# Power.net
KiCad netlist of a schematic drawn in Altium Designer
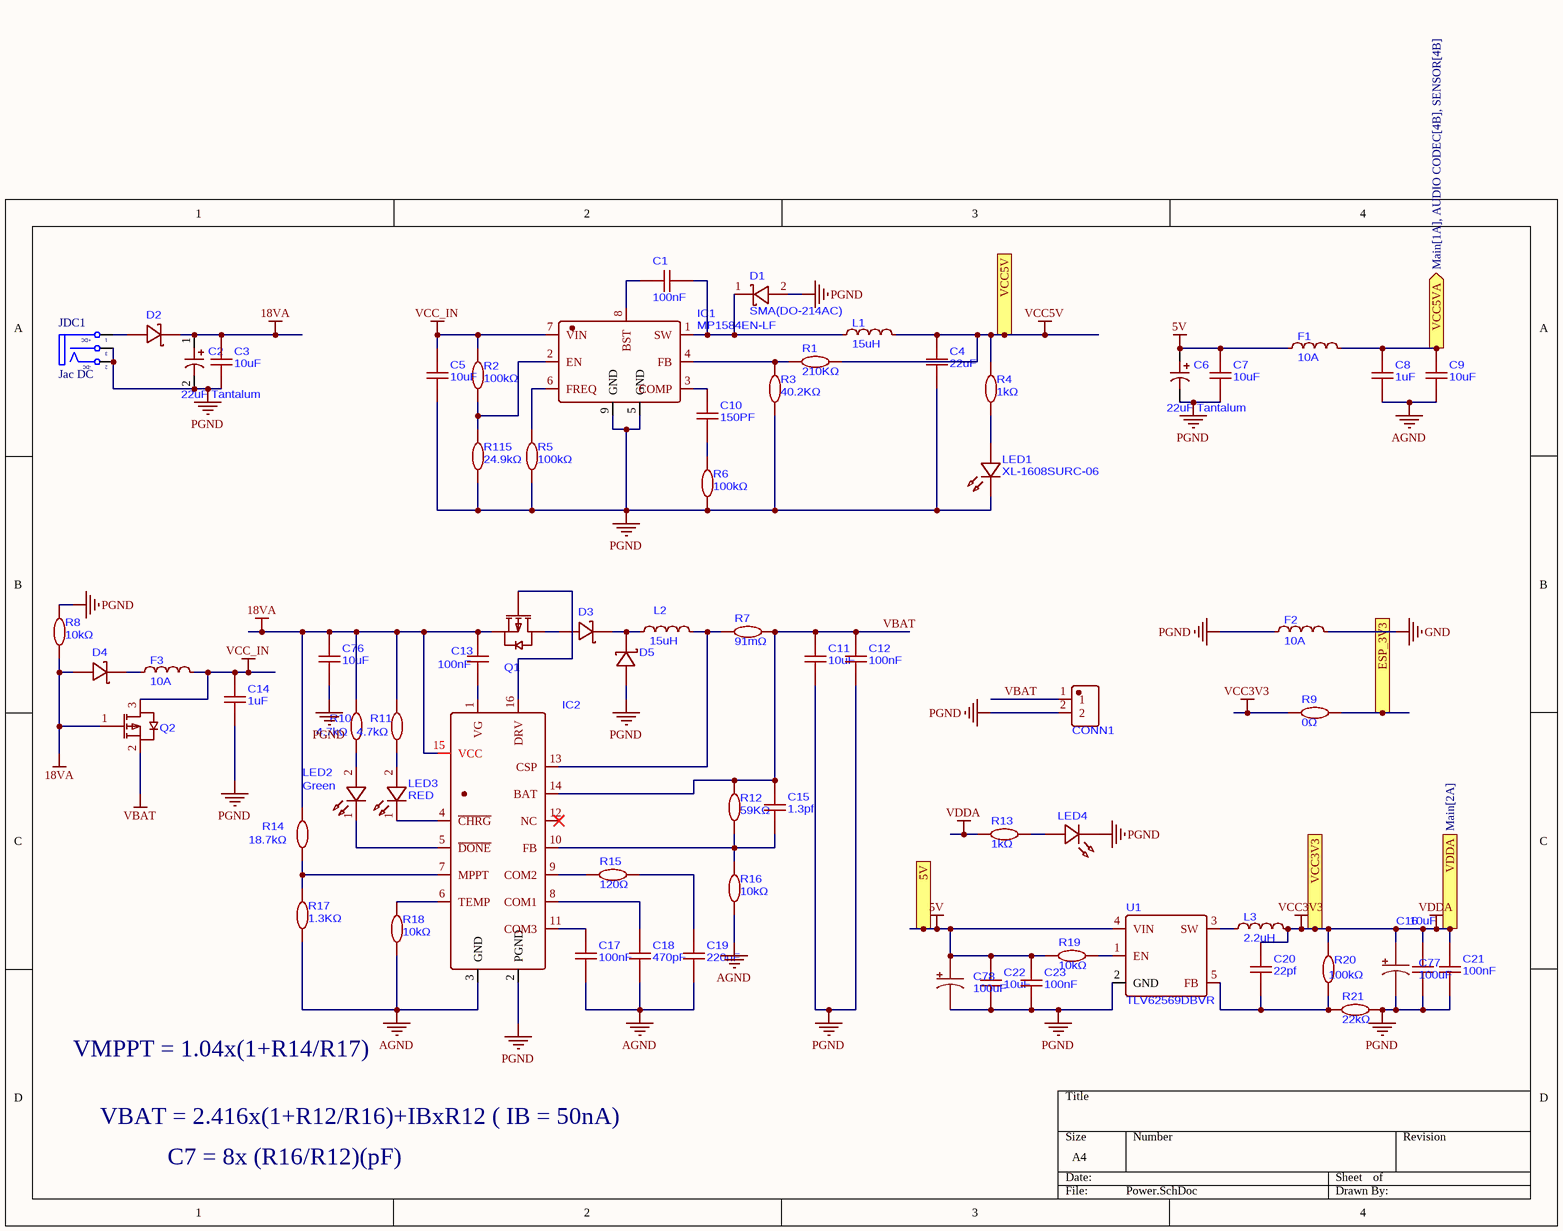
[diagram p0: Power.SchDoc]

(export (version "E")
  (design (tool "Eeschema 10.0.6"))
  (components
    (comp (ref "C1")
      (value "100nF")
      (footprint "C0603")
      (description "50V 100nF X7R ±10% 0603 Ceramic Capacitors ROHS")
      (libsource (lib "Schlib2") (part "CC0603KRX7R9BB104"))
    )
    (comp (ref "C2")
      (value "22uF Tantalum")
      (footprint "CAP-SMD_L7.3-W4.3-R-RD")
      (description "CAP TANT 22uF ±10% 50V CASE-X-7343-43(mm)")
      (libsource (lib "") (part "T491X226K050AT_1"))
    )
    (comp (ref "C3")
      (value "10uF")
      (footprint "C0603")
      (description "25V 10uF X5R ±20% 0603 Ceramic Capacitors ROHS")
      (libsource (lib "Schlib2") (part "CL10A106MA8NRNC"))
    )
    (comp (ref "C4")
      (value "22uF")
      (footprint "C0603")
      (description "10V 22uF X5R ±20% 0603 Ceramic Capacitors ROHS")
      (libsource (lib "Schlib2") (part "CL10A226MP8NUNE"))
    )
    (comp (ref "C5")
      (value "10uF")
      (footprint "C0603")
      (description "25V 10uF X5R ±20% 0603 Ceramic Capacitors ROHS")
      (libsource (lib "Schlib2") (part "CL10A106MA8NRNC"))
    )
    (comp (ref "C6")
      (value "22uF Tantalum")
      (footprint "CAP-SMD_L7.3-W4.3-R-RD")
      (description "CAP TANT 22uF ±10% 50V CASE-X-7343-43(mm)")
      (libsource (lib "Schlib2") (part "T491X226K050AT"))
    )
    (comp (ref "C7")
      (value "10uF")
      (footprint "C0603")
      (description "25V 10uF X5R ±20% 0603 Ceramic Capacitors ROHS")
      (libsource (lib "Schlib2") (part "CL10A106MA8NRNC"))
    )
    (comp (ref "C8")
      (value "1uF")
      (footprint "C0603")
      (description "25V 1uF X7R ±10% 0603 Ceramic Capacitors ROHS")
      (libsource (lib "Schlib2") (part "CL10B105KA8NNNC"))
    )
    (comp (ref "C9")
      (value "10uF")
      (footprint "C0603")
      (description "25V 10uF X5R ±20% 0603 Ceramic Capacitors ROHS")
      (libsource (lib "Schlib2") (part "CL10A106MA8NRNC"))
    )
    (comp (ref "C10")
      (value "150PF")
      (footprint "C0603")
      (description "50V 150pF NP0 ±5% 0603 Ceramic Capacitors ROHS")
      (libsource (lib "Schlib2") (part "CC0603JRNPO9BN151"))
    )
    (comp (ref "C11")
      (value "10uF")
      (footprint "C0603")
      (description "25V 10uF X5R ±20% 0603 Ceramic Capacitors ROHS")
      (libsource (lib "Schlib2") (part "CL10A106MA8NRNC"))
    )
    (comp (ref "C12")
      (value "100nF")
      (footprint "C0603")
      (description "50V 100nF X7R ±10% 0603 Ceramic Capacitors ROHS")
      (libsource (lib "Schlib2") (part "CC0603KRX7R9BB104"))
    )
    (comp (ref "C13")
      (value "100nF")
      (footprint "C0603")
      (description "50V 100nF X7R ±10% 0603 Ceramic Capacitors ROHS")
      (libsource (lib "Schlib2") (part "CC0603KRX7R9BB104"))
    )
    (comp (ref "C14")
      (value "1uF")
      (footprint "C0603")
      (description "25V 1uF X7R ±10% 0603 Ceramic Capacitors ROHS")
      (libsource (lib "Schlib2") (part "CL10B105KA8NNNC"))
    )
    (comp (ref "C15")
      (value "1.3pf")
      (footprint "C0603")
      (description "50V 1.3pF NP0 0603 Ceramic Capacitors ROHS")
      (libsource (lib "Schlib2") (part "CC0603CRNPO9BN1R3"))
    )
    (comp (ref "C16")
      (value "10uF")
      (footprint "C0603")
      (description "10V 10uF X5R ±10% 0603 Ceramic Capacitors ROHS")
      (libsource (lib "Schlib2") (part "CL10A106KP8NNNC"))
    )
    (comp (ref "C17")
      (value "100nF")
      (footprint "C0603")
      (description "50V 100nF X7R ±10% 0603 Ceramic Capacitors ROHS")
      (libsource (lib "Schlib2") (part "CC0603KRX7R9BB104"))
    )
    (comp (ref "C18")
      (value "470pF")
      (footprint "C0603")
      (description "50V 470pF C0G ±5% 0603 Ceramic Capacitors ROHS")
      (libsource (lib "Schlib2") (part "CL10C471JB8NNNC"))
    )
    (comp (ref "C19")
      (value "220nF")
      (footprint "C0603")
      (description "50V 220nF X7R ±10% 0603 Ceramic Capacitors ROHS")
      (libsource (lib "Schlib2") (part "CL10B224KB8NNNC"))
    )
    (comp (ref "C20")
      (value "22pf")
      (footprint "C0603")
      (description "50V 22pF C0G ±5% 0603 Ceramic Capacitors RoHS")
      (libsource (lib "Schlib2") (part "CL10C220JB8NNNC"))
    )
    (comp (ref "C21")
      (value "100nF")
      (footprint "C0603")
      (description "50V 100nF X7R ±10% 0603 Ceramic Capacitors ROHS")
      (libsource (lib "Schlib2") (part "CC0603KRX7R9BB104"))
    )
    (comp (ref "C22")
      (value "10uF")
      (footprint "C0603")
      (description "10V 10uF X5R ±10% 0603 Ceramic Capacitors ROHS")
      (libsource (lib "Schlib2") (part "CL10A106KP8NNNC"))
    )
    (comp (ref "C23")
      (value "100nF")
      (footprint "C0603")
      (description "50V 100nF X7R ±10% 0603 Ceramic Capacitors ROHS")
      (libsource (lib "Schlib2") (part "CC0603KRX7R9BB104"))
    )
    (comp (ref "C76")
      (value "10uF")
      (footprint "C0603")
      (description "25V 10uF X5R ±20% 0603 Ceramic Capacitors ROHS")
      (libsource (lib "Schlib2") (part "CL10A106MA8NRNC"))
    )
    (comp (ref "C77")
      (value "100uF")
      (footprint "CAP-SMD_L3.5-W2.8-R-RD")
      (description "100uF 10V ±10% CASE-B-3528-19(mm) Tantalum Capacitors RoHS")
      (libsource (lib "Schlib2") (part "CA45A-B-10V-100UF-K"))
    )
    (comp (ref "C78")
      (value "100uF")
      (footprint "CAP-SMD_L3.5-W2.8-R-RD")
      (description "100uF 10V ±10% CASE-B-3528-19(mm) Tantalum Capacitors RoHS")
      (libsource (lib "Schlib2") (part "CA45A-B-10V-100UF-K"))
    )
    (comp (ref "CONN1")
      (value "TERM BLK 2POS 5mm TH")
      (footprint "CONN-TH_P5.00_KF128-5.0-2P")
      (libsource (lib "Schlib2") (part "KF128-5.0-2P"))
    )
    (comp (ref "D1")
      (value "SMA(DO-214AC)")
      (footprint "SMA_L4.4-W2.6-LS5.0-RD")
      (description "80A 40V 500mV@3A 3A SMA(DO-214AC) Single Diodes ROHS")
      (libsource (lib "Schlib2") (part "B340A-13-F"))
    )
    (comp (ref "D2")
      (value "B540CQ-13-F")
      (footprint "SMC_L6.9-W5.9-LS7.9-RD")
      (description "40V 550mV@5A 5A SMC(DO-214AB) Single Diodes ROHS")
      (libsource (lib "Schlib2") (part "B540CQ-13-F"))
    )
    (comp (ref "D3")
      (value "B540CQ-13-F")
      (footprint "SMC_L6.9-W5.9-LS7.9-RD")
      (description "40V 550mV@5A 5A SMC(DO-214AB) Single Diodes ROHS")
      (libsource (lib "Schlib2") (part "B540CQ-13-F"))
    )
    (comp (ref "D4")
      (value "B540CQ-13-F")
      (footprint "SMC_L6.9-W5.9-LS7.9-RD")
      (description "40V 550mV@5A 5A SMC(DO-214AB) Single Diodes ROHS")
      (libsource (lib "Schlib2") (part "B540CQ-13-F"))
    )
    (comp (ref "D5")
      (value "B540CQ-13-F")
      (footprint "SMC_L6.9-W5.9-LS7.9-RD")
      (description "40V 550mV@5A 5A SMC(DO-214AB) Single Diodes ROHS")
      (libsource (lib "Schlib2") (part "B540CQ-13-F"))
    )
    (comp (ref "F1")
      (value "10A")
      (footprint "IND-SMD_L8.5-W3.1")
      (description "4mΩ 100Ω@100MHz SMD,8.5x3.1mm Ferrite Beads and Chips ROHS")
      (libsource (lib "Schlib2") (part "HI3312X101R-10"))
    )
    (comp (ref "F2")
      (value "10A")
      (footprint "IND-SMD_L8.5-W3.1")
      (description "4mΩ 100Ω@100MHz SMD,8.5x3.1mm Ferrite Beads and Chips ROHS")
      (libsource (lib "Schlib2") (part "HI3312X101R-10"))
    )
    (comp (ref "F3")
      (value "10A")
      (footprint "IND-SMD_L8.5-W3.1")
      (description "4mΩ 100Ω@100MHz SMD,8.5x3.1mm Ferrite Beads and Chips ROHS")
      (libsource (lib "Schlib2") (part "HI3312X101R-10"))
    )
    (comp (ref "IC1")
      (value "MP1584EN-LF")
      (footprint "SOIC-8_L4.9-W3.9-P1.27-LS6.0-BL-EP3.3")
      (description "Buck Switching Regulator IC")
      (libsource (lib "Schlib2") (part "MP1584EN-LF"))
    )
    (comp (ref "IC2")
      (value "5A TSSOP-16 Battery Management ROHS")
      (footprint "TSSOP-16_L5.0-W4.4-P0.65-LS6.4-BL")
      (libsource (lib "Schlib2") (part "CN3722"))
    )
    (comp (ref "JDC1")
      (value "Jac DC")
      (footprint "DC-IN")
      (description "Jac DC input")
      (libsource (lib "syhaunguyen") (part "DCIN"))
    )
    (comp (ref "L1")
      (value "15uH")
      (footprint "IND-SMD_L10.1-W10.0")
      (description "3.4A 15uH Magnetic Shielded Inductor ±20% 41mΩ SMD,10.1x10.1mm Fixed Inductors ROHS")
      (libsource (lib "Schlib2") (part "YDRH105R-150M"))
    )
    (comp (ref "L2")
      (value "15uH")
      (footprint "IND-SMD_L10.1-W10.0")
      (description "3.4A 15uH Magnetic Shielded Inductor ±20% 41mΩ SMD,10.1x10.1mm Fixed Inductors ROHS")
      (libsource (lib "Schlib2") (part "YDRH105R-150M"))
    )
    (comp (ref "L3")
      (value "2.2uH")
      (footprint "IND-SMD_L5.4-W5.2")
      (description "7A 2.2uH Molded Inductor ±20% 7A 29mΩ SMD,5.4x5.2mm Fixed Inductors RoHS")
      (libsource (lib "Schlib2") (part "APH0530T2R2M"))
    )
    (comp (ref "LED1")
      (value "XL-1608SURC-06")
      (footprint "LED0603-RD_RED")
      (description "20mA 2.3V Red 50mW 0603 LED Indication - Discrete ROHS")
      (libsource (lib "Schlib2") (part "XL-1608SURC-06"))
    )
    (comp (ref "LED2")
      (value "Green")
      (footprint "LED0603-RD_RED")
      (description "5mA 500mcd 526nm~532nm Green 70mW 2.8V 0603 LED Indication - Discrete ROHS")
      (libsource (lib "Schlib2") (part "D-060306G1/SS2/G1"))
    )
    (comp (ref "LED3")
      (value "RED")
      (footprint "LED0603-RD_RED")
      (description "20mA 2.3V Red 50mW 0603 LED Indication - Discrete ROHS")
      (libsource (lib "") (part "XL-1608SURC-06_1"))
    )
    (comp (ref "LED4")
      (value "XL-1608SURC-06")
      (footprint "LED0603-RD_RED")
      (description "20mA 2.3V Red 50mW 0603 LED Indication - Discrete ROHS")
      (libsource (lib "Schlib2") (part "XL-1608SURC-06"))
    )
    (comp (ref "Q1")
      (value "MOSFET P-CH 30V 4.3A SOT-23")
      (footprint "SOT-23-3_L2.9-W1.6-P1.90-LS2.8-BR")
      (description "30V 4.3A 48mΩ@10V 2.5V@250uA 1 P-Channel SOT-23 Single FETs, MOSFETs ROHS")
      (libsource (lib "") (part "AO3407A_1"))
    )
    (comp (ref "Q2")
      (value "MOSFET P-CH 30V 4.3A SOT-23")
      (footprint "SOT-23-3_L2.9-W1.6-P1.90-LS2.8-BR")
      (description "30V 4.3A 48mΩ@10V 2.5V@250uA 1 P-Channel SOT-23 Single FETs, MOSFETs ROHS")
      (libsource (lib "Schlib2") (part "AO3407A"))
    )
    (comp (ref "R1")
      (value "210KΩ")
      (footprint "R0603")
      (description "100mW 210kΩ 75V ±100ppm/℃ Thick Film Resistor ±1% 0603 Chip Resistor - Surface Mount ROHS")
      (libsource (lib "Schlib2") (part "0603WAF2103T5E"))
    )
    (comp (ref "R2")
      (value "100kΩ")
      (footprint "R0603")
      (description "100mW 100kΩ 75V ±100ppm/℃ Thick Film Resistor ±1% 0603 Chip Resistor - Surface Mount ROHS")
      (libsource (lib "Schlib2") (part "RC0603FR-07100KL"))
    )
    (comp (ref "R3")
      (value "40.2KΩ")
      (footprint "R0603")
      (description "40.2kΩ 100mW 75V ±25ppm/℃ Thin Film Resistor ±0.1% 0603 Chip Resistor - Surface Mount ROHS")
      (libsource (lib "Schlib2") (part "RT0603BRD0740K2L"))
    )
    (comp (ref "R4")
      (value "1kΩ")
      (footprint "R0603")
      (description "100mW 1kΩ 50V ±100ppm/℃ Thick Film Resistor ±5% 0603 Chip Resistor - Surface Mount ROHS")
      (libsource (lib "Schlib2") (part "RMC 0603 1K J N"))
    )
    (comp (ref "R5")
      (value "100kΩ")
      (footprint "R0603")
      (description "100mW 100kΩ 75V ±100ppm/℃ Thick Film Resistor ±1% 0603 Chip Resistor - Surface Mount ROHS")
      (libsource (lib "Schlib2") (part "RC0603FR-07100KL"))
    )
    (comp (ref "R6")
      (value "100kΩ")
      (footprint "R0603")
      (description "100mW 100kΩ 75V ±100ppm/℃ Thick Film Resistor ±1% 0603 Chip Resistor - Surface Mount ROHS")
      (libsource (lib "Schlib2") (part "RC0603FR-07100KL"))
    )
    (comp (ref "R7")
      (value "91mΩ")
      (footprint "R1206")
      (description "250mW 91mΩ 500V ±600ppm/℃ Thick Film Resistor ±1% 1206 Chip Resistor - Surface Mount ROHS")
      (libsource (lib "Schlib2") (part "FRL1206FR091TS"))
    )
    (comp (ref "R8")
      (value "10kΩ")
      (footprint "R0603")
      (description "100mW 10kΩ 75V ±100ppm/℃ Thick Film Resistor ±1% 0603 Chip Resistor - Surface Mount ROHS")
      (libsource (lib "Schlib2") (part "RC0603FR-0710KL"))
    )
    (comp (ref "R9")
      (value "0Ω")
      (footprint "R0603")
      (description "100mW 0Ω 75V Thick Film Resistor ±5% 0603 Chip Resistor - Surface Mount RoHS")
      (libsource (lib "Schlib2") (part "RC0603JR-070RL"))
    )
    (comp (ref "R10")
      (value "4.7kΩ")
      (footprint "R0603")
      (description "100mW 4.7kΩ 75V ±100ppm/℃ Thick Film Resistor ±1% 0603 Chip Resistor - Surface Mount ROHS")
      (libsource (lib "Schlib2") (part "RC0603FR-074K7L"))
    )
    (comp (ref "R11")
      (value "4.7kΩ")
      (footprint "R0603")
      (description "100mW 4.7kΩ 75V ±100ppm/℃ Thick Film Resistor ±1% 0603 Chip Resistor - Surface Mount ROHS")
      (libsource (lib "Schlib2") (part "RC0603FR-074K7L"))
    )
    (comp (ref "R12")
      (value "59KΩ")
      (footprint "R0603")
      (description "100mW 59kΩ 75V ±100ppm/℃ Thick Film Resistor ±1% 0603 Chip Resistor - Surface Mount ROHS")
      (libsource (lib "Schlib2") (part "FRC0603F5902TS"))
    )
    (comp (ref "R13")
      (value "1kΩ")
      (footprint "R0603")
      (description "100mW 1kΩ 50V ±100ppm/℃ Thick Film Resistor ±5% 0603 Chip Resistor - Surface Mount ROHS")
      (libsource (lib "Schlib2") (part "RMC 0603 1K J N"))
    )
    (comp (ref "R14")
      (value "18.7kΩ")
      (footprint "R0603")
      (description "100mW 18.7kΩ 75V ±100ppm/℃ Thick Film Resistor ±1% 0603 Chip Resistor - Surface Mount ROHS")
      (libsource (lib "Schlib2") (part "FRC0603F1872TS"))
    )
    (comp (ref "R15")
      (value "120Ω")
      (footprint "R0603")
      (description "100mW 120Ω 75V ±100ppm/℃ Thick Film Resistor ±1% 0603 Chip Resistor - Surface Mount ROHS")
      (libsource (lib "Schlib2") (part "0603WAF1200T5E"))
    )
    (comp (ref "R16")
      (value "10kΩ")
      (footprint "R0603")
      (description "100mW 10kΩ 75V ±100ppm/℃ Thick Film Resistor ±1% 0603 Chip Resistor - Surface Mount ROHS")
      (libsource (lib "Schlib2") (part "RC0603FR-0710KL"))
    )
    (comp (ref "R17")
      (value "1.3KΩ")
      (footprint "R0603")
      (description "100mW 1.3kΩ 75V ±25ppm/℃ Thin Film Resistor ±0.1% 0603 Chip Resistor - Surface Mount ROHS")
      (libsource (lib "Schlib2") (part "RT0603BRD071K3L"))
    )
    (comp (ref "R18")
      (value "10kΩ")
      (footprint "R0603")
      (description "100mW 10kΩ 75V ±100ppm/℃ Thick Film Resistor ±1% 0603 Chip Resistor - Surface Mount ROHS")
      (libsource (lib "Schlib2") (part "RC0603FR-0710KL"))
    )
    (comp (ref "R19")
      (value "10kΩ")
      (footprint "R0603")
      (description "100mW 10kΩ 75V ±100ppm/℃ Thick Film Resistor ±1% 0603 Chip Resistor - Surface Mount ROHS")
      (libsource (lib "Schlib2") (part "RC0603FR-0710KL"))
    )
    (comp (ref "R20")
      (value "100kΩ")
      (footprint "R0603")
      (description "100mW 100kΩ 75V ±100ppm/℃ Thick Film Resistor ±1% 0603 Chip Resistor - Surface Mount ROHS")
      (libsource (lib "Schlib2") (part "RC0603FR-07100KL"))
    )
    (comp (ref "R21")
      (value "22kΩ")
      (footprint "R0603")
      (description "100mW 22kΩ 75V ±100ppm/℃ Thick Film Resistor ±1% 0603 Chip Resistor - Surface Mount RoHS")
      (libsource (lib "Schlib2") (part "RC0603FR-0722KL"))
    )
    (comp (ref "R115")
      (value "24.9kΩ")
      (footprint "R0603")
      (description "1100mW 24.9kΩ 75V ±100ppm/℃ Thick Film Resistor ±1% 0603 Chip Resistor - Surface Mount ROHS")
      (libsource (lib "Schlib2") (part "0603WAF2492T5E"))
    )
    (comp (ref "U1")
      (value "TLV62569DBVR")
      (footprint "SOT-23-5_L3.0-W1.7-P0.95-LS2.8-BR")
      (libsource (lib "Schlib2") (part "TLV62569DBVR"))
    )
  )
  (nets
    (net (code "1") (name "/ESP_3V3") (class "Default")
      (node (ref "R9") (pin "2") (pinfunction "2_2") (pintype "passive"))
    )
    (net (code "2") (name "/VCC5VA") (class "Default")
      (node (ref "C8") (pin "1") (pinfunction "1_1") (pintype "passive"))
      (node (ref "C9") (pin "2") (pinfunction "2_2") (pintype "passive"))
      (node (ref "F1") (pin "2") (pinfunction "2_2") (pintype "passive"))
    )
    (net (code "3") (name "5V") (class "Default")
      (node (ref "C22") (pin "2") (pinfunction "2_2") (pintype "passive"))
      (node (ref "C23") (pin "2") (pinfunction "2_2") (pintype "passive"))
      (node (ref "C6") (pin "1") (pinfunction "1_1") (pintype "passive"))
      (node (ref "C7") (pin "2") (pinfunction "2_2") (pintype "passive"))
      (node (ref "C78") (pin "1") (pinfunction "1_1") (pintype "passive"))
      (node (ref "F1") (pin "1") (pinfunction "1_1") (pintype "passive"))
      (node (ref "R19") (pin "1") (pinfunction "1_1") (pintype "passive"))
      (node (ref "U1") (pin "4") (pinfunction "VIN_4") (pintype "passive"))
    )
    (net (code "4") (name "18VA") (class "Default")
      (node (ref "C13") (pin "2") (pinfunction "2_2") (pintype "passive"))
      (node (ref "C2") (pin "1") (pinfunction "1_1") (pintype "passive"))
      (node (ref "C3") (pin "2") (pinfunction "2_2") (pintype "passive"))
      (node (ref "C76") (pin "2") (pinfunction "2_2") (pintype "passive"))
      (node (ref "D2") (pin "1") (pinfunction "C_1") (pintype "passive"))
      (node (ref "D4") (pin "2") (pinfunction "A_2") (pintype "passive"))
      (node (ref "IC2") (pin "15") (pinfunction "VCC_15") (pintype "passive"))
      (node (ref "Q1") (pin "2") (pinfunction "S_2") (pintype "passive"))
      (node (ref "Q2") (pin "1") (pinfunction "G_1") (pintype "passive"))
      (node (ref "R10") (pin "2") (pinfunction "2_2") (pintype "passive"))
      (node (ref "R11") (pin "2") (pinfunction "2_2") (pintype "passive"))
      (node (ref "R14") (pin "2") (pinfunction "2_2") (pintype "passive"))
      (node (ref "R8") (pin "1") (pinfunction "1_1") (pintype "passive"))
    )
    (net (code "5") (name "AGND") (class "Default")
      (node (ref "C17") (pin "1") (pinfunction "1_1") (pintype "passive"))
      (node (ref "C18") (pin "1") (pinfunction "1_1") (pintype "passive"))
      (node (ref "C19") (pin "1") (pinfunction "1_1") (pintype "passive"))
      (node (ref "C8") (pin "2") (pinfunction "2_2") (pintype "passive"))
      (node (ref "C9") (pin "1") (pinfunction "1_1") (pintype "passive"))
      (node (ref "IC2") (pin "3") (pinfunction "GND_3") (pintype "passive"))
      (node (ref "R16") (pin "1") (pinfunction "1_1") (pintype "passive"))
      (node (ref "R17") (pin "1") (pinfunction "1_1") (pintype "passive"))
      (node (ref "R18") (pin "1") (pinfunction "1_1") (pintype "passive"))
    )
    (net (code "6") (name "GND") (class "Default")
      (node (ref "F2") (pin "2") (pinfunction "2_2") (pintype "passive"))
    )
    (net (code "7") (name "Net-(C10-Pad1)") (class "Default")
      (node (ref "C10") (pin "1") (pinfunction "1_1") (pintype "passive"))
      (node (ref "R6") (pin "2") (pinfunction "2_2") (pintype "passive"))
    )
    (net (code "8") (name "Net-(C19-Pad2)") (class "Default")
      (node (ref "C19") (pin "2") (pinfunction "2_2") (pintype "passive"))
      (node (ref "R15") (pin "2") (pinfunction "2_2") (pintype "passive"))
    )
    (net (code "9") (name "Net-(D1-K)") (class "Default")
      (node (ref "C1") (pin "2") (pinfunction "2_2") (pintype "passive"))
      (node (ref "D1") (pin "1") (pinfunction "K_1") (pintype "passive"))
      (node (ref "IC1") (pin "1") (pinfunction "SW_1") (pintype "passive"))
      (node (ref "L1") (pin "1") (pinfunction "1_1") (pintype "passive"))
    )
    (net (code "10") (name "Net-(D2-A)") (class "Default")
      (node (ref "D2") (pin "2") (pinfunction "A_2") (pintype "passive"))
      (node (ref "JDC1") (pin "1") (pinfunction "T_1") (pintype "passive"))
    )
    (net (code "11") (name "Net-(D3-A)") (class "Default")
      (node (ref "D3") (pin "2") (pinfunction "A_2") (pintype "passive"))
      (node (ref "Q1") (pin "3") (pinfunction "D_3") (pintype "passive"))
    )
    (net (code "12") (name "Net-(D3-C)") (class "Default")
      (node (ref "D3") (pin "1") (pinfunction "C_1") (pintype "passive"))
      (node (ref "D5") (pin "1") (pinfunction "C_1") (pintype "passive"))
      (node (ref "L2") (pin "1") (pinfunction "1_1") (pintype "passive"))
    )
    (net (code "13") (name "Net-(D4-C)") (class "Default")
      (node (ref "D4") (pin "1") (pinfunction "C_1") (pintype "passive"))
      (node (ref "F3") (pin "1") (pinfunction "1_1") (pintype "passive"))
    )
    (net (code "14") (name "Net-(IC1-BST)") (class "Default")
      (node (ref "C1") (pin "1") (pinfunction "1_1") (pintype "passive"))
      (node (ref "IC1") (pin "8") (pinfunction "BST_8") (pintype "passive"))
    )
    (net (code "15") (name "Net-(IC1-COMP)") (class "Default")
      (node (ref "C10") (pin "2") (pinfunction "2_2") (pintype "passive"))
      (node (ref "IC1") (pin "3") (pinfunction "COMP_3") (pintype "passive"))
    )
    (net (code "16") (name "Net-(IC1-EN)") (class "Default")
      (node (ref "IC1") (pin "2") (pinfunction "EN_2") (pintype "passive"))
      (node (ref "R115") (pin "2") (pinfunction "2_2") (pintype "passive"))
      (node (ref "R2") (pin "1") (pinfunction "1_1") (pintype "passive"))
    )
    (net (code "17") (name "Net-(IC1-FB)") (class "Default")
      (node (ref "IC1") (pin "4") (pinfunction "FB_4") (pintype "passive"))
      (node (ref "R1") (pin "1") (pinfunction "1_1") (pintype "passive"))
      (node (ref "R3") (pin "2") (pinfunction "2_2") (pintype "passive"))
    )
    (net (code "18") (name "Net-(IC1-FREQ)") (class "Default")
      (node (ref "IC1") (pin "6") (pinfunction "FREQ_6") (pintype "passive"))
      (node (ref "R5") (pin "2") (pinfunction "2_2") (pintype "passive"))
    )
    (net (code "19") (name "Net-(IC2-COM1)") (class "Default")
      (node (ref "C18") (pin "2") (pinfunction "2_2") (pintype "passive"))
      (node (ref "IC2") (pin "8") (pinfunction "COM1_8") (pintype "passive"))
    )
    (net (code "20") (name "Net-(IC2-COM2)") (class "Default")
      (node (ref "IC2") (pin "9") (pinfunction "COM2_9") (pintype "passive"))
      (node (ref "R15") (pin "1") (pinfunction "1_1") (pintype "passive"))
    )
    (net (code "21") (name "Net-(IC2-COM3)") (class "Default")
      (node (ref "C17") (pin "2") (pinfunction "2_2") (pintype "passive"))
      (node (ref "IC2") (pin "11") (pinfunction "COM3_11") (pintype "passive"))
    )
    (net (code "22") (name "Net-(IC2-CSP)") (class "Default")
      (node (ref "IC2") (pin "13") (pinfunction "CSP_13") (pintype "passive"))
      (node (ref "L2") (pin "2") (pinfunction "2_2") (pintype "passive"))
      (node (ref "R7") (pin "1") (pinfunction "1_1") (pintype "passive"))
    )
    (net (code "23") (name "Net-(IC2-DRV)") (class "Default")
      (node (ref "IC2") (pin "16") (pinfunction "DRV_16") (pintype "passive"))
      (node (ref "Q1") (pin "1") (pinfunction "G_1") (pintype "passive"))
    )
    (net (code "24") (name "Net-(IC2-FB)") (class "Default")
      (node (ref "C15") (pin "1") (pinfunction "1_1") (pintype "passive"))
      (node (ref "IC2") (pin "10") (pinfunction "FB_10") (pintype "passive"))
      (node (ref "R12") (pin "1") (pinfunction "1_1") (pintype "passive"))
      (node (ref "R16") (pin "2") (pinfunction "2_2") (pintype "passive"))
    )
    (net (code "25") (name "Net-(IC2-MPPT)") (class "Default")
      (node (ref "IC2") (pin "7") (pinfunction "MPPT_7") (pintype "passive"))
      (node (ref "R14") (pin "1") (pinfunction "1_1") (pintype "passive"))
      (node (ref "R17") (pin "2") (pinfunction "2_2") (pintype "passive"))
    )
    (net (code "26") (name "Net-(IC2-TEMP)") (class "Default")
      (node (ref "IC2") (pin "6") (pinfunction "TEMP_6") (pintype "passive"))
      (node (ref "R18") (pin "2") (pinfunction "2_2") (pintype "passive"))
    )
    (net (code "27") (name "Net-(IC2-VG)") (class "Default")
      (node (ref "C13") (pin "1") (pinfunction "1_1") (pintype "passive"))
      (node (ref "IC2") (pin "1") (pinfunction "VG_1") (pintype "passive"))
    )
    (net (code "28") (name "Net-(IC2-~{CHRG})") (class "Default")
      (node (ref "IC2") (pin "4") (pinfunction "~{CHRG}_4") (pintype "passive"))
      (node (ref "LED3") (pin "1") (pinfunction "K_1") (pintype "passive"))
    )
    (net (code "29") (name "Net-(IC2-~{DONE})") (class "Default")
      (node (ref "IC2") (pin "5") (pinfunction "~{DONE}_5") (pintype "passive"))
      (node (ref "LED2") (pin "1") (pinfunction "K_1") (pintype "passive"))
    )
    (net (code "30") (name "Net-(LED1-A)") (class "Default")
      (node (ref "LED1") (pin "2") (pinfunction "A_2") (pintype "passive"))
      (node (ref "R4") (pin "1") (pinfunction "1_1") (pintype "passive"))
    )
    (net (code "31") (name "Net-(LED2-A)") (class "Default")
      (node (ref "LED2") (pin "2") (pinfunction "A_2") (pintype "passive"))
      (node (ref "R10") (pin "1") (pinfunction "1_1") (pintype "passive"))
    )
    (net (code "32") (name "Net-(LED3-A)") (class "Default")
      (node (ref "LED3") (pin "2") (pinfunction "A_2") (pintype "passive"))
      (node (ref "R11") (pin "1") (pinfunction "1_1") (pintype "passive"))
    )
    (net (code "33") (name "Net-(LED4-A)") (class "Default")
      (node (ref "LED4") (pin "2") (pinfunction "A_2") (pintype "passive"))
      (node (ref "R13") (pin "1") (pinfunction "1_1") (pintype "passive"))
    )
    (net (code "34") (name "Net-(U1-EN)") (class "Default")
      (node (ref "R19") (pin "2") (pinfunction "2_2") (pintype "passive"))
      (node (ref "U1") (pin "1") (pinfunction "EN_1") (pintype "passive"))
    )
    (net (code "35") (name "Net-(U1-FB)") (class "Default")
      (node (ref "C20") (pin "1") (pinfunction "1_1") (pintype "passive"))
      (node (ref "R20") (pin "1") (pinfunction "1_1") (pintype "passive"))
      (node (ref "R21") (pin "1") (pinfunction "1_1") (pintype "passive"))
      (node (ref "U1") (pin "5") (pinfunction "FB_5") (pintype "passive"))
    )
    (net (code "36") (name "Net-(U1-SW)") (class "Default")
      (node (ref "L3") (pin "1") (pinfunction "1_1") (pintype "passive"))
      (node (ref "U1") (pin "3") (pinfunction "SW_3") (pintype "passive"))
    )
    (net (code "37") (name "PGND") (class "Default")
      (node (ref "C11") (pin "1") (pinfunction "1_1") (pintype "passive"))
      (node (ref "C12") (pin "1") (pinfunction "1_1") (pintype "passive"))
      (node (ref "C14") (pin "2") (pinfunction "2_2") (pintype "passive"))
      (node (ref "C16") (pin "1") (pinfunction "1_1") (pintype "passive"))
      (node (ref "C2") (pin "2") (pinfunction "2_2") (pintype "passive"))
      (node (ref "C21") (pin "1") (pinfunction "1_1") (pintype "passive"))
      (node (ref "C22") (pin "1") (pinfunction "1_1") (pintype "passive"))
      (node (ref "C23") (pin "1") (pinfunction "1_1") (pintype "passive"))
      (node (ref "C3") (pin "1") (pinfunction "1_1") (pintype "passive"))
      (node (ref "C4") (pin "1") (pinfunction "1_1") (pintype "passive"))
      (node (ref "C5") (pin "1") (pinfunction "1_1") (pintype "passive"))
      (node (ref "C6") (pin "2") (pinfunction "2_2") (pintype "passive"))
      (node (ref "C7") (pin "1") (pinfunction "1_1") (pintype "passive"))
      (node (ref "C76") (pin "1") (pinfunction "1_1") (pintype "passive"))
      (node (ref "C77") (pin "2") (pinfunction "2_2") (pintype "passive"))
      (node (ref "C78") (pin "2") (pinfunction "2_2") (pintype "passive"))
      (node (ref "CONN1") (pin "2") (pinfunction "2_2") (pintype "passive"))
      (node (ref "D1") (pin "2") (pinfunction "A_2") (pintype "passive"))
      (node (ref "D5") (pin "2") (pinfunction "A_2") (pintype "passive"))
      (node (ref "F2") (pin "1") (pinfunction "1_1") (pintype "passive"))
      (node (ref "IC1") (pin "5") (pinfunction "GND_5") (pintype "passive"))
      (node (ref "IC1") (pin "9") (pinfunction "GND_9") (pintype "passive"))
      (node (ref "IC2") (pin "2") (pinfunction "PGND_2") (pintype "passive"))
      (node (ref "JDC1") (pin "2") (pinfunction "TN_2") (pintype "passive"))
      (node (ref "JDC1") (pin "3") (pinfunction "S_3") (pintype "power_in"))
      (node (ref "LED1") (pin "1") (pinfunction "K_1") (pintype "passive"))
      (node (ref "LED4") (pin "1") (pinfunction "K_1") (pintype "passive"))
      (node (ref "R115") (pin "1") (pinfunction "1_1") (pintype "passive"))
      (node (ref "R21") (pin "2") (pinfunction "2_2") (pintype "passive"))
      (node (ref "R3") (pin "1") (pinfunction "1_1") (pintype "passive"))
      (node (ref "R5") (pin "1") (pinfunction "1_1") (pintype "passive"))
      (node (ref "R6") (pin "1") (pinfunction "1_1") (pintype "passive"))
      (node (ref "R8") (pin "2") (pinfunction "2_2") (pintype "passive"))
      (node (ref "U1") (pin "2") (pinfunction "GND_2") (pintype "passive"))
    )
    (net (code "38") (name "VBAT") (class "Default")
      (node (ref "C11") (pin "2") (pinfunction "2_2") (pintype "passive"))
      (node (ref "C12") (pin "2") (pinfunction "2_2") (pintype "passive"))
      (node (ref "C15") (pin "2") (pinfunction "2_2") (pintype "passive"))
      (node (ref "CONN1") (pin "1") (pinfunction "1_1") (pintype "passive"))
      (node (ref "IC2") (pin "14") (pinfunction "BAT_14") (pintype "passive"))
      (node (ref "Q2") (pin "2") (pinfunction "S_2") (pintype "passive"))
      (node (ref "R12") (pin "2") (pinfunction "2_2") (pintype "passive"))
      (node (ref "R7") (pin "2") (pinfunction "2_2") (pintype "passive"))
    )
    (net (code "39") (name "VCC3V3") (class "Default")
      (node (ref "C16") (pin "2") (pinfunction "2_2") (pintype "passive"))
      (node (ref "C20") (pin "2") (pinfunction "2_2") (pintype "passive"))
      (node (ref "C21") (pin "2") (pinfunction "2_2") (pintype "passive"))
      (node (ref "C77") (pin "1") (pinfunction "1_1") (pintype "passive"))
      (node (ref "L3") (pin "2") (pinfunction "2_2") (pintype "passive"))
      (node (ref "R13") (pin "2") (pinfunction "2_2") (pintype "passive"))
      (node (ref "R20") (pin "2") (pinfunction "2_2") (pintype "passive"))
      (node (ref "R9") (pin "1") (pinfunction "1_1") (pintype "passive"))
    )
    (net (code "40") (name "VCC5V") (class "Default")
      (node (ref "C4") (pin "2") (pinfunction "2_2") (pintype "passive"))
      (node (ref "L1") (pin "2") (pinfunction "2_2") (pintype "passive"))
      (node (ref "R1") (pin "2") (pinfunction "2_2") (pintype "passive"))
      (node (ref "R4") (pin "2") (pinfunction "2_2") (pintype "passive"))
    )
    (net (code "41") (name "VCC_IN") (class "Default")
      (node (ref "C14") (pin "1") (pinfunction "1_1") (pintype "passive"))
      (node (ref "C5") (pin "2") (pinfunction "2_2") (pintype "passive"))
      (node (ref "F3") (pin "2") (pinfunction "2_2") (pintype "passive"))
      (node (ref "IC1") (pin "7") (pinfunction "VIN_7") (pintype "passive"))
      (node (ref "Q2") (pin "3") (pinfunction "D_3") (pintype "passive"))
      (node (ref "R2") (pin "2") (pinfunction "2_2") (pintype "passive"))
    )
    (net (code "42") (name "unconnected-(IC2-NC-Pad12)") (class "Default")
      (node (ref "IC2") (pin "12") (pinfunction "NC_12") (pintype "passive+no_connect"))
    )
  )
)
